# 12_Raspbbery_CM3.net
KiCad netlist of a schematic drawn in Altium Designer
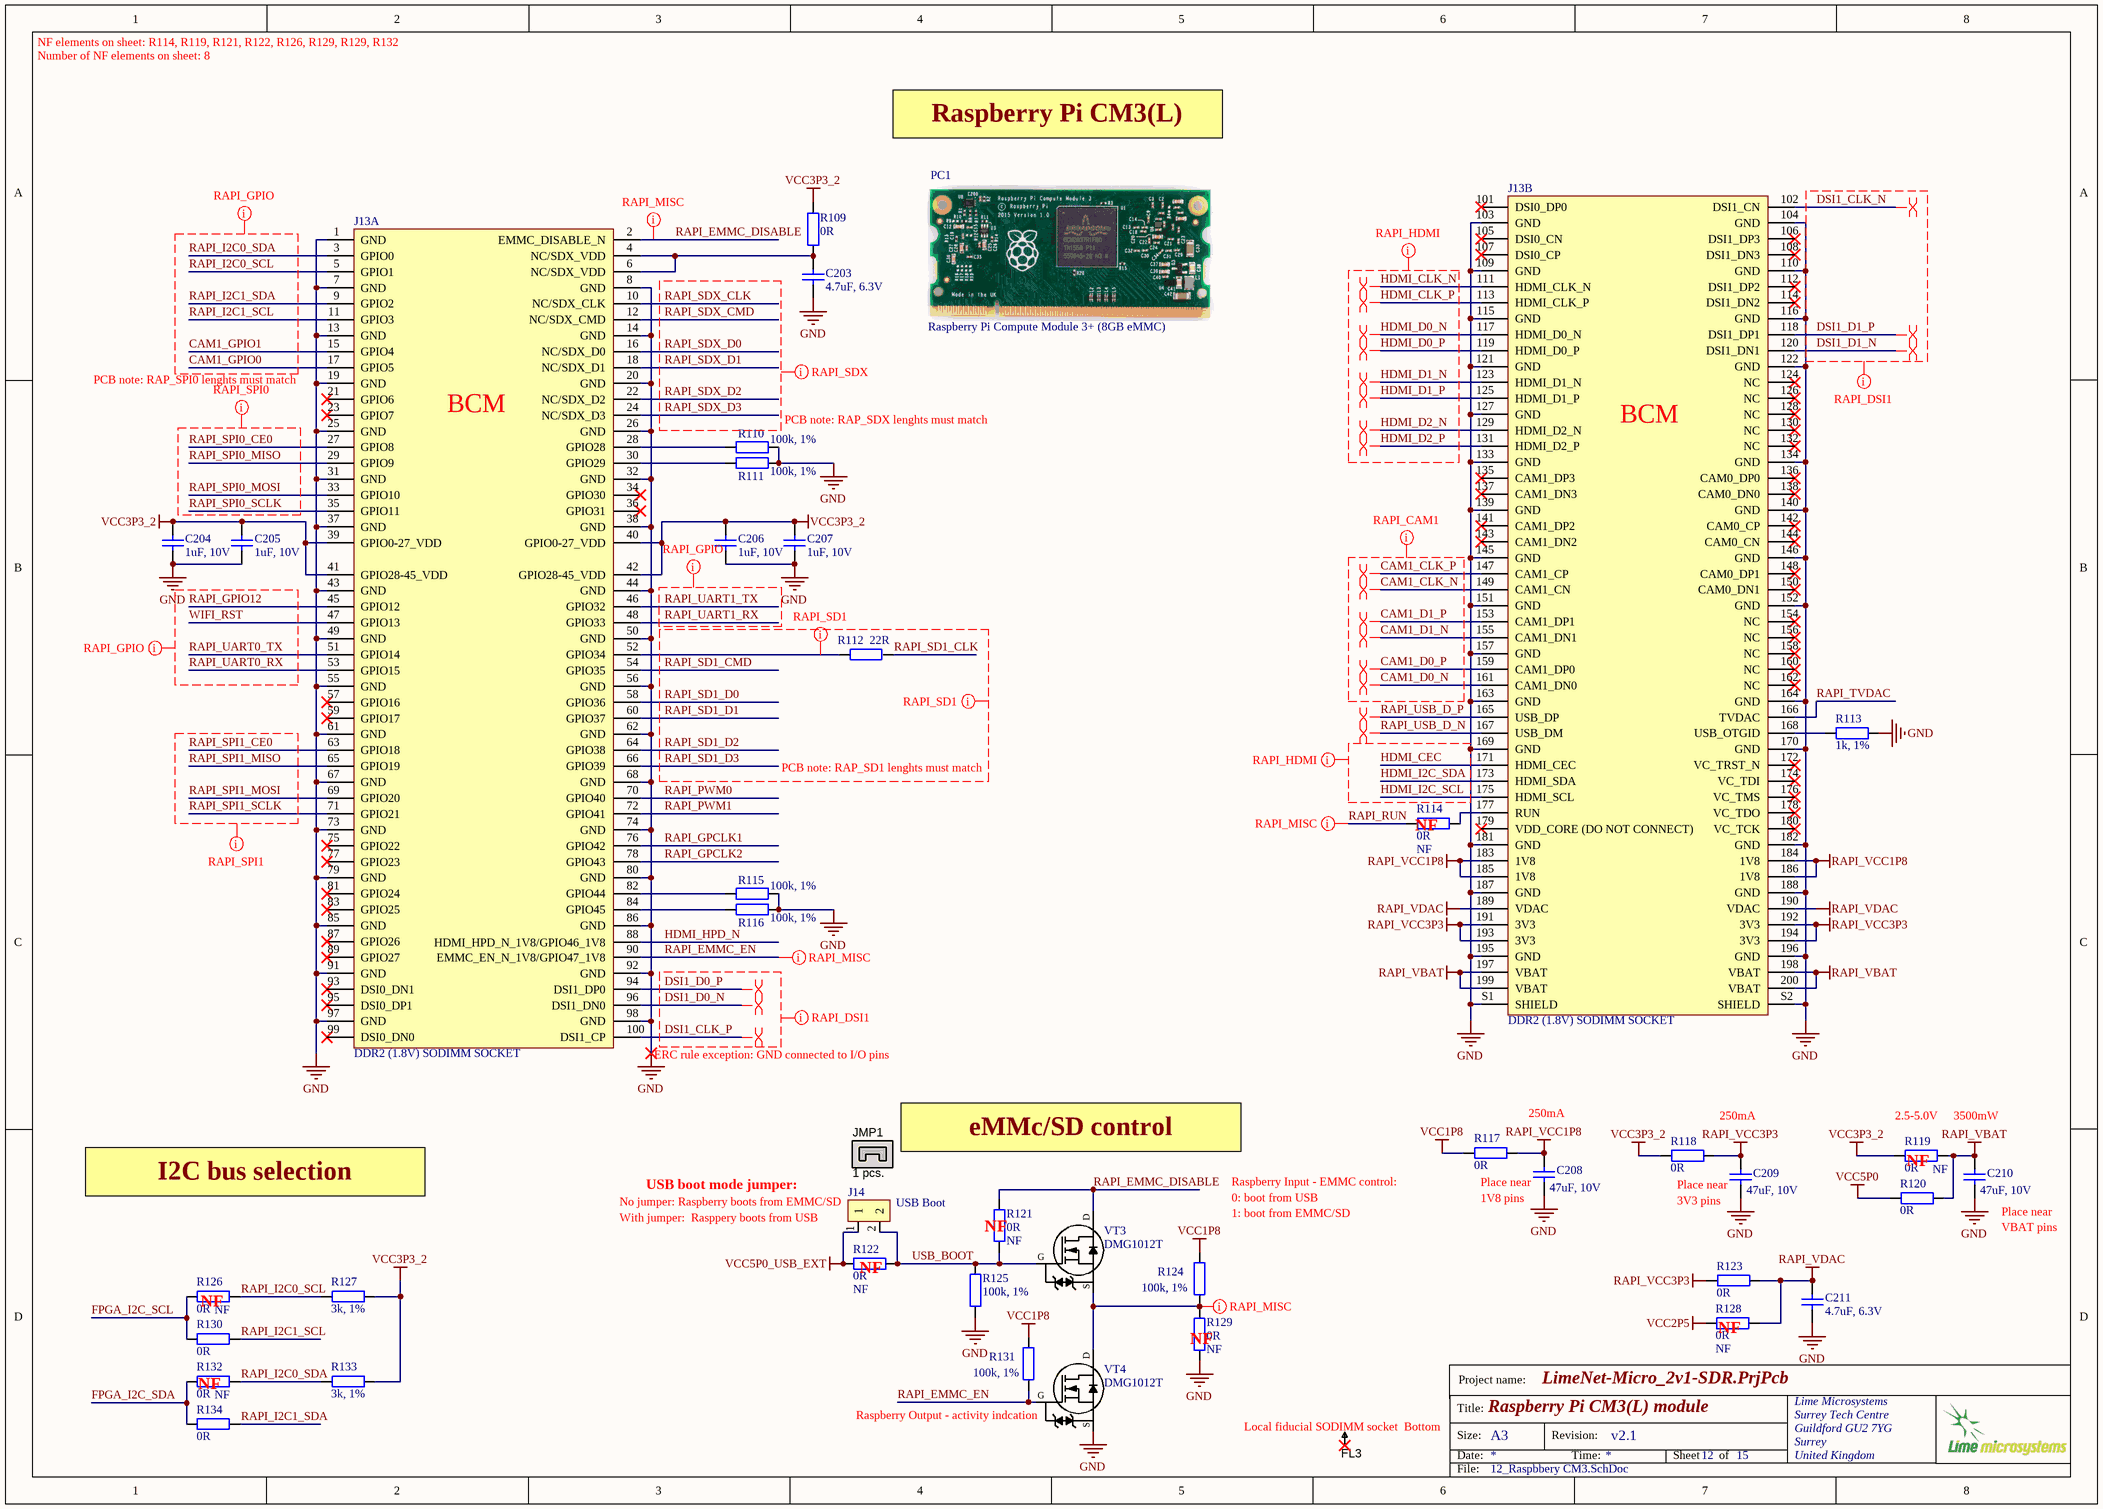
[diagram p0: 12_Raspbbery CM3.SchDoc]

(export (version "E")
  (design (tool "Eeschema 10.0.6"))
  (components
    (comp (ref "C203")
      (value "4.7uF, 6.3V")
      (footprint "CAP0402")
      (fields
        (field (name "MANUFACTURER") "Murata Electronics North America")
        (field (name "TOLERANCE") "±20%")
      )
      (libsource (lib "LimeMicroAltiumLib_schLib") (part "Cap_0402"))
    )
    (comp (ref "C204")
      (value "1uF, 10V")
      (footprint "CAP0402")
      (description "CAP CER 1UF 10V X5R 0402")
      (fields (field (name "MANUFACTURER") "Yageo") (field (name "TOLERANCE") "±20%"))
      (libsource (lib "LimeMicroAltiumLib_schLib") (part "Cap_0402"))
    )
    (comp (ref "C205")
      (value "1uF, 10V")
      (footprint "CAP0402")
      (description "CAP CER 1UF 10V X5R 0402")
      (fields (field (name "MANUFACTURER") "Yageo") (field (name "TOLERANCE") "±20%"))
      (libsource (lib "LimeMicroAltiumLib_schLib") (part "Cap_0402"))
    )
    (comp (ref "C206")
      (value "1uF, 10V")
      (footprint "CAP0402")
      (description "CAP CER 1UF 10V X5R 0402")
      (fields (field (name "MANUFACTURER") "Yageo") (field (name "TOLERANCE") "±20%"))
      (libsource (lib "LimeMicroAltiumLib_schLib") (part "Cap_0402"))
    )
    (comp (ref "C207")
      (value "1uF, 10V")
      (footprint "CAP0402")
      (description "CAP CER 1UF 10V X5R 0402")
      (fields (field (name "MANUFACTURER") "Yageo") (field (name "TOLERANCE") "±20%"))
      (libsource (lib "LimeMicroAltiumLib_schLib") (part "Cap_0402"))
    )
    (comp (ref "C208")
      (value "47uF, 10V")
      (footprint "CAP1206")
      (fields (field (name "TOLERANCE") "±20%") (field (name "MANUFACTURER") "TDK Corporation"))
      (libsource (lib "LimeFPGAboard_schLib") (part "Cap_1206"))
    )
    (comp (ref "C209")
      (value "47uF, 10V")
      (footprint "CAP1206")
      (fields (field (name "TOLERANCE") "±20%") (field (name "MANUFACTURER") "TDK Corporation"))
      (libsource (lib "LimeFPGAboard_schLib") (part "Cap_1206"))
    )
    (comp (ref "C210")
      (value "47uF, 10V")
      (footprint "CAP1206")
      (fields (field (name "TOLERANCE") "±20%") (field (name "MANUFACTURER") "TDK Corporation"))
      (libsource (lib "LimeFPGAboard_schLib") (part "Cap_1206"))
    )
    (comp (ref "C211")
      (value "4.7uF, 6.3V")
      (footprint "CAP0402")
      (fields
        (field (name "MANUFACTURER") "Murata Electronics North America")
        (field (name "TOLERANCE") "±20%")
      )
      (libsource (lib "LimeMicroAltiumLib_schLib") (part "Cap_0402"))
    )
    (comp (ref "FL3")
      (value "Fiducial")
      (footprint "Fiducial_local")
      (libsource (lib "VGTU_Altium_lib") (part "Fiducial"))
    )
    (comp (ref "J13")
      (value "DDR2 (1.8V) SODIMM SOCKET")
      (footprint "TE_1717254-1_DDR_SODIMM")
      (fields (field (name "MANUFACTURER") "TE Connectivity AMP Connectors"))
      (libsource (lib "LimeMicroAltiumLib_schLib_r01") (part "1717254-1"))
    )
    (comp (ref "J14")
      (value "USB Boot")
      (footprint "HDR_1x2")
      (fields (field (name "MANUFACTURER") "3M"))
      (libsource (lib "LimeFPGAboard_schLib") (part "Jumper"))
    )
    (comp (ref "JMP1")
      (value "1 pcs.")
      (description "Shorting Jumper, 2-position, 1.27mm pitch")
      (fields (field (name "MANUFACTURER") "Sullins"))
      (libsource (lib "LimeMicroAltiumLib_schLib") (part "JUMP_2P_CONN_HEADER"))
    )
    (comp (ref "PC1")
      (value "Raspberry Pi Compute Module 3+ (8GB eMMC)")
      (fields (field (name "MANUFACTURER") "RASPBERRY-PI"))
      (libsource (lib "LimeMicroAltiumLib_schLib_r01") (part "Raspberry_RPI-COMPUTE3"))
    )
    (comp (ref "R109")
      (value "0R")
      (footprint "RES0402")
      (fields (field (name "MANUFACTURER") "Yageo") (field (name "TOLERANCE") "Jumper"))
      (libsource (lib "LimeFPGAboard_schLib") (part "Res_0402"))
    )
    (comp (ref "R110")
      (value "100k, 1%")
      (footprint "RES0402")
      (fields
        (field (name "MANUFACTURER") "Vishay Dale")
        (field (name "TOLERANCE") "±1%")
        (field (name "MANUFACTURER PART NUMBER") "CRCW0402100KFKEDC")
      )
      (libsource (lib "LimeMicroAltiumLib_schLib") (part "Res_0402"))
    )
    (comp (ref "R111")
      (value "100k, 1%")
      (footprint "RES0402")
      (fields
        (field (name "MANUFACTURER") "Vishay Dale")
        (field (name "TOLERANCE") "±1%")
        (field (name "MANUFACTURER PART NUMBER") "CRCW0402100KFKEDC")
      )
      (libsource (lib "LimeMicroAltiumLib_schLib") (part "Res_0402"))
    )
    (comp (ref "R112")
      (value "22R")
      (footprint "RES0402")
      (fields (field (name "TOLERANCE") "±1%") (field (name "MANUFACTURER") "Yageo"))
      (libsource (lib "LimeFPGAboard_schLib") (part "Res_0402"))
    )
    (comp (ref "R113")
      (value "1k, 1%")
      (footprint "RES0402")
      (fields (field (name "MANUFACTURER") "Stackpole Electronics Inc") (field (name "TOLERANCE") "±1%"))
      (libsource (lib "LimeMicroAltiumLib_schLib") (part "Res_0402"))
    )
    (comp (ref "R114")
      (value "0R")
      (footprint "RES0402")
      (fields
        (field (name "MANUFACTURER") "Yageo")
        (field (name "ASSEMBLY INFO") "NF")
        (field (name "TOLERANCE") "Jumper")
      )
      (libsource (lib "LimeFPGAboard_schLib") (part "Res_0402"))
    )
    (comp (ref "R115")
      (value "100k, 1%")
      (footprint "RES0402")
      (fields
        (field (name "MANUFACTURER") "Vishay Dale")
        (field (name "TOLERANCE") "±1%")
        (field (name "MANUFACTURER PART NUMBER") "CRCW0402100KFKEDC")
      )
      (libsource (lib "LimeMicroAltiumLib_schLib") (part "Res_0402"))
    )
    (comp (ref "R116")
      (value "100k, 1%")
      (footprint "RES0402")
      (fields
        (field (name "MANUFACTURER") "Vishay Dale")
        (field (name "TOLERANCE") "±1%")
        (field (name "MANUFACTURER PART NUMBER") "CRCW0402100KFKEDC")
      )
      (libsource (lib "LimeMicroAltiumLib_schLib") (part "Res_0402"))
    )
    (comp (ref "R117")
      (value "0R")
      (footprint "RES0805")
      (fields (field (name "MANUFACTURER") "Vishay Dale") (field (name "TOLERANCE") "Jumper"))
      (libsource (lib "LimeMicroAltiumLib_schLib") (part "Res_0402"))
    )
    (comp (ref "R118")
      (value "0R")
      (footprint "RES0805")
      (fields (field (name "MANUFACTURER") "Vishay Dale") (field (name "TOLERANCE") "Jumper"))
      (libsource (lib "LimeMicroAltiumLib_schLib") (part "Res_0402"))
    )
    (comp (ref "R119")
      (value "0R")
      (footprint "RES0805")
      (fields
        (field (name "ASSEMBLY INFO") "NF")
        (field (name "MANUFACTURER") "Vishay Dale")
        (field (name "TOLERANCE") "Jumper")
      )
      (libsource (lib "LimeMicroAltiumLib_schLib") (part "Res_0402"))
    )
    (comp (ref "R120")
      (value "0R")
      (footprint "RES0805")
      (fields (field (name "MANUFACTURER") "Vishay Dale") (field (name "TOLERANCE") "Jumper"))
      (libsource (lib "LimeMicroAltiumLib_schLib") (part "Res_0402"))
    )
    (comp (ref "R121")
      (value "0R")
      (footprint "RES0402")
      (fields
        (field (name "MANUFACTURER") "Yageo")
        (field (name "ASSEMBLY INFO") "NF")
        (field (name "TOLERANCE") "Jumper")
      )
      (libsource (lib "LimeFPGAboard_schLib") (part "Res_0402"))
    )
    (comp (ref "R122")
      (value "0R")
      (footprint "RES0402")
      (fields
        (field (name "ASSEMBLY INFO") "NF")
        (field (name "MANUFACTURER") "Yageo")
        (field (name "TOLERANCE") "Jumper")
      )
      (libsource (lib "LimeMicroAltiumLib_schLib") (part "Res_0402"))
    )
    (comp (ref "R123")
      (value "0R")
      (footprint "RES0402")
      (fields (field (name "MANUFACTURER") "Yageo") (field (name "TOLERANCE") "Jumper"))
      (libsource (lib "LimeFPGAboard_schLib") (part "Res_0402"))
    )
    (comp (ref "R124")
      (value "100k, 1%")
      (footprint "RES0402")
      (fields
        (field (name "MANUFACTURER") "Vishay Dale")
        (field (name "TOLERANCE") "±1%")
        (field (name "MANUFACTURER PART NUMBER") "CRCW0402100KFKEDC")
      )
      (libsource (lib "LimeMicroAltiumLib_schLib") (part "Res_0402"))
    )
    (comp (ref "R125")
      (value "100k, 1%")
      (footprint "RES0402")
      (fields
        (field (name "MANUFACTURER") "Vishay Dale")
        (field (name "TOLERANCE") "±1%")
        (field (name "MANUFACTURER PART NUMBER") "CRCW0402100KFKEDC")
      )
      (libsource (lib "LimeMicroAltiumLib_schLib") (part "Res_0402"))
    )
    (comp (ref "R126")
      (value "0R")
      (footprint "RES0402")
      (fields
        (field (name "MANUFACTURER") "Yageo")
        (field (name "ASSEMBLY INFO") "NF")
        (field (name "TOLERANCE") "Jumper")
      )
      (libsource (lib "LimeFPGAboard_schLib") (part "Res_0402"))
    )
    (comp (ref "R127")
      (value "3k, 1%")
      (footprint "RES0402")
      (fields (field (name "TOLERANCE") "±1%") (field (name "MANUFACTURER") "Vishay Dale"))
      (libsource (lib "LimeMicroAltiumLib_schLib") (part "Res_0402"))
    )
    (comp (ref "R128")
      (value "0R")
      (footprint "RES0402")
      (fields
        (field (name "MANUFACTURER") "Yageo")
        (field (name "ASSEMBLY INFO") "NF")
        (field (name "TOLERANCE") "Jumper")
      )
      (libsource (lib "LimeFPGAboard_schLib") (part "Res_0402"))
    )
    (comp (ref "R129")
      (value "0R")
      (footprint "RES0402")
      (fields
        (field (name "MANUFACTURER") "Yageo")
        (field (name "ASSEMBLY INFO") "NF")
        (field (name "TOLERANCE") "Jumper")
      )
      (libsource (lib "LimeFPGAboard_schLib") (part "Res_0402"))
    )
    (comp (ref "R130")
      (value "0R")
      (footprint "RES0402")
      (fields (field (name "MANUFACTURER") "Yageo") (field (name "TOLERANCE") "Jumper"))
      (libsource (lib "LimeFPGAboard_schLib") (part "Res_0402"))
    )
    (comp (ref "R131")
      (value "100k, 1%")
      (footprint "RES0402")
      (fields
        (field (name "MANUFACTURER") "Vishay Dale")
        (field (name "TOLERANCE") "±1%")
        (field (name "MANUFACTURER PART NUMBER") "CRCW0402100KFKEDC")
      )
      (libsource (lib "LimeMicroAltiumLib_schLib") (part "Res_0402"))
    )
    (comp (ref "R132")
      (value "0R")
      (footprint "RES0402")
      (fields
        (field (name "MANUFACTURER") "Yageo")
        (field (name "ASSEMBLY INFO") "NF")
        (field (name "TOLERANCE") "Jumper")
      )
      (libsource (lib "LimeFPGAboard_schLib") (part "Res_0402"))
    )
    (comp (ref "R133")
      (value "3k, 1%")
      (footprint "RES0402")
      (fields (field (name "TOLERANCE") "±1%") (field (name "MANUFACTURER") "Vishay Dale"))
      (libsource (lib "LimeMicroAltiumLib_schLib") (part "Res_0402"))
    )
    (comp (ref "R134")
      (value "0R")
      (footprint "RES0402")
      (fields (field (name "MANUFACTURER") "Yageo") (field (name "TOLERANCE") "Jumper"))
      (libsource (lib "LimeFPGAboard_schLib") (part "Res_0402"))
    )
    (comp (ref "VT3")
      (value "DMG1012T")
      (footprint "SOT523")
      (fields (field (name "MANUFACTURER") "Diodes Incorporated"))
      (libsource (lib "LimeMicroAltiumLib_schLib_r01") (part "DMG1012T"))
    )
    (comp (ref "VT4")
      (value "DMG1012T")
      (footprint "SOT523")
      (fields (field (name "MANUFACTURER") "Diodes Incorporated"))
      (libsource (lib "LimeMicroAltiumLib_schLib_r01") (part "DMG1012T"))
    )
  )
  (nets
    (net (code "1") (name "/CAM1_CLK_N") (class "Default")
      (node (ref "J13") (pin "149") (pinfunction "CAM1_CN_149") (pintype "passive"))
    )
    (net (code "2") (name "/CAM1_CLK_P") (class "Default")
      (node (ref "J13") (pin "147") (pinfunction "CAM1_CP_147") (pintype "passive"))
    )
    (net (code "3") (name "/CAM1_D0_N") (class "Default")
      (node (ref "J13") (pin "161") (pinfunction "CAM1_DN0_161") (pintype "passive"))
    )
    (net (code "4") (name "/CAM1_D0_P") (class "Default")
      (node (ref "J13") (pin "159") (pinfunction "CAM1_DP0_159") (pintype "passive"))
    )
    (net (code "5") (name "/CAM1_D1_N") (class "Default")
      (node (ref "J13") (pin "155") (pinfunction "CAM1_DN1_155") (pintype "passive"))
    )
    (net (code "6") (name "/CAM1_D1_P") (class "Default")
      (node (ref "J13") (pin "153") (pinfunction "CAM1_DP1_153") (pintype "passive"))
    )
    (net (code "7") (name "/CAM1_GPIO0") (class "Default")
      (node (ref "J13") (pin "17") (pinfunction "GPIO5_17") (pintype "passive"))
    )
    (net (code "8") (name "/CAM1_GPIO1") (class "Default")
      (node (ref "J13") (pin "15") (pinfunction "GPIO4_15") (pintype "passive"))
    )
    (net (code "9") (name "/DSI1_CLK_N") (class "Default")
      (node (ref "J13") (pin "102") (pinfunction "DSI1_CN_102") (pintype "passive"))
    )
    (net (code "10") (name "/DSI1_CLK_P") (class "Default")
      (node (ref "J13") (pin "100") (pinfunction "DSI1_CP_100") (pintype "passive"))
    )
    (net (code "11") (name "/DSI1_D0_N") (class "Default")
      (node (ref "J13") (pin "96") (pinfunction "DSI1_DN0_96") (pintype "passive"))
    )
    (net (code "12") (name "/DSI1_D0_P") (class "Default")
      (node (ref "J13") (pin "94") (pinfunction "DSI1_DP0_94") (pintype "passive"))
    )
    (net (code "13") (name "/DSI1_D1_N") (class "Default")
      (node (ref "J13") (pin "120") (pinfunction "DSI1_DN1_120") (pintype "passive"))
    )
    (net (code "14") (name "/DSI1_D1_P") (class "Default")
      (node (ref "J13") (pin "118") (pinfunction "DSI1_DP1_118") (pintype "passive"))
    )
    (net (code "15") (name "/FPGA_I2C_SCL") (class "Default")
      (node (ref "R126") (pin "1") (pinfunction "1_1") (pintype "passive"))
      (node (ref "R130") (pin "1") (pinfunction "1_1") (pintype "passive"))
    )
    (net (code "16") (name "/FPGA_I2C_SDA") (class "Default")
      (node (ref "R132") (pin "1") (pinfunction "1_1") (pintype "passive"))
      (node (ref "R134") (pin "1") (pinfunction "1_1") (pintype "passive"))
    )
    (net (code "17") (name "/HDMI_CEC") (class "Default")
      (node (ref "J13") (pin "171") (pinfunction "HDMI_CEC_171") (pintype "passive"))
    )
    (net (code "18") (name "/HDMI_CLK_N") (class "Default")
      (node (ref "J13") (pin "111") (pinfunction "HDMI_CLK_N_111") (pintype "passive"))
    )
    (net (code "19") (name "/HDMI_CLK_P") (class "Default")
      (node (ref "J13") (pin "113") (pinfunction "HDMI_CLK_P_113") (pintype "passive"))
    )
    (net (code "20") (name "/HDMI_D0_N") (class "Default")
      (node (ref "J13") (pin "117") (pinfunction "HDMI_D0_N_117") (pintype "passive"))
    )
    (net (code "21") (name "/HDMI_D0_P") (class "Default")
      (node (ref "J13") (pin "119") (pinfunction "HDMI_D0_P_119") (pintype "passive"))
    )
    (net (code "22") (name "/HDMI_D1_N") (class "Default")
      (node (ref "J13") (pin "123") (pinfunction "HDMI_D1_N_123") (pintype "passive"))
    )
    (net (code "23") (name "/HDMI_D1_P") (class "Default")
      (node (ref "J13") (pin "125") (pinfunction "HDMI_D1_P_125") (pintype "passive"))
    )
    (net (code "24") (name "/HDMI_D2_N") (class "Default")
      (node (ref "J13") (pin "129") (pinfunction "HDMI_D2_N_129") (pintype "passive"))
    )
    (net (code "25") (name "/HDMI_D2_P") (class "Default")
      (node (ref "J13") (pin "131") (pinfunction "HDMI_D2_P_131") (pintype "passive"))
    )
    (net (code "26") (name "/HDMI_HPD_N") (class "Default")
      (node (ref "J13") (pin "88") (pinfunction "HDMI_HPD_N_1V8/GPIO46_1V8_88") (pintype "passive"))
    )
    (net (code "27") (name "/HDMI_I2C_SCL") (class "Default")
      (node (ref "J13") (pin "175") (pinfunction "HDMI_SCL_175") (pintype "passive"))
    )
    (net (code "28") (name "/HDMI_I2C_SDA") (class "Default")
      (node (ref "J13") (pin "173") (pinfunction "HDMI_SDA_173") (pintype "passive"))
    )
    (net (code "29") (name "/RAPI_EMMC_DISABLE") (class "Default")
      (node (ref "J13") (pin "2") (pinfunction "EMMC_DISABLE_N_2") (pintype "passive"))
      (node (ref "R121") (pin "1") (pinfunction "1_1") (pintype "passive"))
      (node (ref "VT3") (pin "D") (pinfunction "D_D") (pintype "passive"))
    )
    (net (code "30") (name "/RAPI_EMMC_EN") (class "Default")
      (node (ref "J13") (pin "90") (pinfunction "EMMC_EN_N_1V8/GPIO47_1V8_90") (pintype "passive"))
      (node (ref "R131") (pin "2") (pinfunction "2_2") (pintype "passive"))
      (node (ref "VT4") (pin "G") (pinfunction "G_G") (pintype "passive"))
    )
    (net (code "31") (name "/RAPI_GPCLK1") (class "Default")
      (node (ref "J13") (pin "76") (pinfunction "GPIO42_76") (pintype "passive"))
    )
    (net (code "32") (name "/RAPI_GPCLK2") (class "Default")
      (node (ref "J13") (pin "78") (pinfunction "GPIO43_78") (pintype "passive"))
    )
    (net (code "33") (name "/RAPI_GPIO12") (class "Default")
      (node (ref "J13") (pin "45") (pinfunction "GPIO12_45") (pintype "passive"))
    )
    (net (code "34") (name "/RAPI_I2C0_SCL") (class "Default")
      (node (ref "J13") (pin "5") (pinfunction "GPIO1_5") (pintype "passive"))
      (node (ref "R126") (pin "2") (pinfunction "2_2") (pintype "passive"))
      (node (ref "R127") (pin "2") (pinfunction "2_2") (pintype "passive"))
    )
    (net (code "35") (name "/RAPI_I2C0_SDA") (class "Default")
      (node (ref "J13") (pin "3") (pinfunction "GPIO0_3") (pintype "passive"))
      (node (ref "R132") (pin "2") (pinfunction "2_2") (pintype "passive"))
      (node (ref "R133") (pin "2") (pinfunction "2_2") (pintype "passive"))
    )
    (net (code "36") (name "/RAPI_I2C1_SCL") (class "Default")
      (node (ref "J13") (pin "11") (pinfunction "GPIO3_11") (pintype "passive"))
      (node (ref "R130") (pin "2") (pinfunction "2_2") (pintype "passive"))
    )
    (net (code "37") (name "/RAPI_I2C1_SDA") (class "Default")
      (node (ref "J13") (pin "9") (pinfunction "GPIO2_9") (pintype "passive"))
      (node (ref "R134") (pin "2") (pinfunction "2_2") (pintype "passive"))
    )
    (net (code "38") (name "/RAPI_PWM0") (class "Default")
      (node (ref "J13") (pin "70") (pinfunction "GPIO40_70") (pintype "passive"))
    )
    (net (code "39") (name "/RAPI_PWM1") (class "Default")
      (node (ref "J13") (pin "72") (pinfunction "GPIO41_72") (pintype "passive"))
    )
    (net (code "40") (name "/RAPI_RUN") (class "Default")
      (node (ref "R114") (pin "2") (pinfunction "2_2") (pintype "passive"))
    )
    (net (code "41") (name "/RAPI_SD1_CLK") (class "Default")
      (node (ref "R112") (pin "2") (pinfunction "2_2") (pintype "passive"))
    )
    (net (code "42") (name "/RAPI_SD1_CMD") (class "Default")
      (node (ref "J13") (pin "54") (pinfunction "GPIO35_54") (pintype "passive"))
    )
    (net (code "43") (name "/RAPI_SD1_D0") (class "Default")
      (node (ref "J13") (pin "58") (pinfunction "GPIO36_58") (pintype "passive"))
    )
    (net (code "44") (name "/RAPI_SD1_D1") (class "Default")
      (node (ref "J13") (pin "60") (pinfunction "GPIO37_60") (pintype "passive"))
    )
    (net (code "45") (name "/RAPI_SD1_D2") (class "Default")
      (node (ref "J13") (pin "64") (pinfunction "GPIO38_64") (pintype "passive"))
    )
    (net (code "46") (name "/RAPI_SD1_D3") (class "Default")
      (node (ref "J13") (pin "66") (pinfunction "GPIO39_66") (pintype "passive"))
    )
    (net (code "47") (name "/RAPI_SDX_CLK") (class "Default")
      (node (ref "J13") (pin "10") (pinfunction "NC/SDX_CLK_10") (pintype "passive"))
    )
    (net (code "48") (name "/RAPI_SDX_CMD") (class "Default")
      (node (ref "J13") (pin "12") (pinfunction "NC/SDX_CMD_12") (pintype "passive"))
    )
    (net (code "49") (name "/RAPI_SDX_D0") (class "Default")
      (node (ref "J13") (pin "16") (pinfunction "NC/SDX_D0_16") (pintype "passive"))
    )
    (net (code "50") (name "/RAPI_SDX_D1") (class "Default")
      (node (ref "J13") (pin "18") (pinfunction "NC/SDX_D1_18") (pintype "passive"))
    )
    (net (code "51") (name "/RAPI_SDX_D2") (class "Default")
      (node (ref "J13") (pin "22") (pinfunction "NC/SDX_D2_22") (pintype "passive"))
    )
    (net (code "52") (name "/RAPI_SDX_D3") (class "Default")
      (node (ref "J13") (pin "24") (pinfunction "NC/SDX_D3_24") (pintype "passive"))
    )
    (net (code "53") (name "/RAPI_SPI0_CE0") (class "Default")
      (node (ref "J13") (pin "27") (pinfunction "GPIO8_27") (pintype "passive"))
    )
    (net (code "54") (name "/RAPI_SPI0_MISO") (class "Default")
      (node (ref "J13") (pin "29") (pinfunction "GPIO9_29") (pintype "passive"))
    )
    (net (code "55") (name "/RAPI_SPI0_MOSI") (class "Default")
      (node (ref "J13") (pin "33") (pinfunction "GPIO10_33") (pintype "passive"))
    )
    (net (code "56") (name "/RAPI_SPI0_SCLK") (class "Default")
      (node (ref "J13") (pin "35") (pinfunction "GPIO11_35") (pintype "passive"))
    )
    (net (code "57") (name "/RAPI_SPI1_CE0") (class "Default")
      (node (ref "J13") (pin "63") (pinfunction "GPIO18_63") (pintype "passive"))
    )
    (net (code "58") (name "/RAPI_SPI1_MISO") (class "Default")
      (node (ref "J13") (pin "65") (pinfunction "GPIO19_65") (pintype "passive"))
    )
    (net (code "59") (name "/RAPI_SPI1_MOSI") (class "Default")
      (node (ref "J13") (pin "69") (pinfunction "GPIO20_69") (pintype "passive"))
    )
    (net (code "60") (name "/RAPI_SPI1_SCLK") (class "Default")
      (node (ref "J13") (pin "71") (pinfunction "GPIO21_71") (pintype "passive"))
    )
    (net (code "61") (name "/RAPI_TVDAC") (class "Default")
      (node (ref "J13") (pin "166") (pinfunction "TVDAC_166") (pintype "passive"))
    )
    (net (code "62") (name "/RAPI_UART0_RX") (class "Default")
      (node (ref "J13") (pin "53") (pinfunction "GPIO15_53") (pintype "passive"))
    )
    (net (code "63") (name "/RAPI_UART0_TX") (class "Default")
      (node (ref "J13") (pin "51") (pinfunction "GPIO14_51") (pintype "passive"))
    )
    (net (code "64") (name "/RAPI_UART1_RX") (class "Default")
      (node (ref "J13") (pin "48") (pinfunction "GPIO33_48") (pintype "passive"))
    )
    (net (code "65") (name "/RAPI_UART1_TX") (class "Default")
      (node (ref "J13") (pin "46") (pinfunction "GPIO32_46") (pintype "passive"))
    )
    (net (code "66") (name "/RAPI_USB_D_N") (class "Default")
      (node (ref "J13") (pin "167") (pinfunction "USB_DM_167") (pintype "passive"))
    )
    (net (code "67") (name "/RAPI_USB_D_P") (class "Default")
      (node (ref "J13") (pin "165") (pinfunction "USB_DP_165") (pintype "passive"))
    )
    (net (code "68") (name "/USB_BOOT") (class "Default")
      (node (ref "J14") (pin "2") (pinfunction "2_2") (pintype "passive"))
      (node (ref "R121") (pin "2") (pinfunction "2_2") (pintype "passive"))
      (node (ref "R122") (pin "2") (pinfunction "2_2") (pintype "passive"))
      (node (ref "R125") (pin "1") (pinfunction "1_1") (pintype "passive"))
      (node (ref "VT3") (pin "G") (pinfunction "G_G") (pintype "passive"))
    )
    (net (code "69") (name "/WIFI_RST") (class "Default")
      (node (ref "J13") (pin "47") (pinfunction "GPIO13_47") (pintype "passive"))
    )
    (net (code "70") (name "GND") (class "Default")
      (node (ref "C203") (pin "2") (pinfunction "2_2") (pintype "passive"))
      (node (ref "C204") (pin "1") (pinfunction "1_1") (pintype "passive"))
      (node (ref "C205") (pin "1") (pinfunction "1_1") (pintype "passive"))
      (node (ref "C206") (pin "1") (pinfunction "1_1") (pintype "passive"))
      (node (ref "C207") (pin "1") (pinfunction "1_1") (pintype "passive"))
      (node (ref "C208") (pin "1") (pinfunction "1_1") (pintype "passive"))
      (node (ref "C209") (pin "1") (pinfunction "1_1") (pintype "passive"))
      (node (ref "C210") (pin "1") (pinfunction "1_1") (pintype "passive"))
      (node (ref "C211") (pin "1") (pinfunction "1_1") (pintype "passive"))
      (node (ref "J13") (pin "1") (pinfunction "GND_1") (pintype "passive"))
      (node (ref "J13") (pin "103") (pinfunction "GND_103") (pintype "passive"))
      (node (ref "J13") (pin "104") (pinfunction "GND_104") (pintype "passive"))
      (node (ref "J13") (pin "109") (pinfunction "GND_109") (pintype "passive"))
      (node (ref "J13") (pin "110") (pinfunction "GND_110") (pintype "passive"))
      (node (ref "J13") (pin "115") (pinfunction "GND_115") (pintype "passive"))
      (node (ref "J13") (pin "116") (pinfunction "GND_116") (pintype "passive"))
      (node (ref "J13") (pin "121") (pinfunction "GND_121") (pintype "passive"))
      (node (ref "J13") (pin "122") (pinfunction "GND_122") (pintype "passive"))
      (node (ref "J13") (pin "127") (pinfunction "GND_127") (pintype "passive"))
      (node (ref "J13") (pin "13") (pinfunction "GND_13") (pintype "passive"))
      (node (ref "J13") (pin "133") (pinfunction "GND_133") (pintype "passive"))
      (node (ref "J13") (pin "134") (pinfunction "GND_134") (pintype "passive"))
      (node (ref "J13") (pin "139") (pinfunction "GND_139") (pintype "passive"))
      (node (ref "J13") (pin "14") (pinfunction "GND_14") (pintype "passive"))
      (node (ref "J13") (pin "140") (pinfunction "GND_140") (pintype "passive"))
      (node (ref "J13") (pin "145") (pinfunction "GND_145") (pintype "passive"))
      (node (ref "J13") (pin "146") (pinfunction "GND_146") (pintype "passive"))
      (node (ref "J13") (pin "151") (pinfunction "GND_151") (pintype "passive"))
      (node (ref "J13") (pin "152") (pinfunction "GND_152") (pintype "passive"))
      (node (ref "J13") (pin "157") (pinfunction "GND_157") (pintype "passive"))
      (node (ref "J13") (pin "163") (pinfunction "GND_163") (pintype "passive"))
      (node (ref "J13") (pin "164") (pinfunction "GND_164") (pintype "passive"))
      (node (ref "J13") (pin "169") (pinfunction "GND_169") (pintype "passive"))
      (node (ref "J13") (pin "170") (pinfunction "GND_170") (pintype "passive"))
      (node (ref "J13") (pin "181") (pinfunction "GND_181") (pintype "passive"))
      (node (ref "J13") (pin "182") (pinfunction "GND_182") (pintype "passive"))
      (node (ref "J13") (pin "187") (pinfunction "GND_187") (pintype "passive"))
      (node (ref "J13") (pin "188") (pinfunction "GND_188") (pintype "passive"))
      (node (ref "J13") (pin "19") (pinfunction "GND_19") (pintype "passive"))
      (node (ref "J13") (pin "195") (pinfunction "GND_195") (pintype "passive"))
      (node (ref "J13") (pin "196") (pinfunction "GND_196") (pintype "passive"))
      (node (ref "J13") (pin "20") (pinfunction "GND_20") (pintype "passive"))
      (node (ref "J13") (pin "25") (pinfunction "GND_25") (pintype "passive"))
      (node (ref "J13") (pin "26") (pinfunction "GND_26") (pintype "passive"))
      (node (ref "J13") (pin "31") (pinfunction "GND_31") (pintype "passive"))
      (node (ref "J13") (pin "32") (pinfunction "GND_32") (pintype "passive"))
      (node (ref "J13") (pin "37") (pinfunction "GND_37") (pintype "passive"))
      (node (ref "J13") (pin "38") (pinfunction "GND_38") (pintype "passive"))
      (node (ref "J13") (pin "43") (pinfunction "GND_43") (pintype "passive"))
      (node (ref "J13") (pin "44") (pinfunction "GND_44") (pintype "passive"))
      (node (ref "J13") (pin "49") (pinfunction "GND_49") (pintype "passive"))
      (node (ref "J13") (pin "50") (pinfunction "GND_50") (pintype "passive"))
      (node (ref "J13") (pin "55") (pinfunction "GND_55") (pintype "passive"))
      (node (ref "J13") (pin "56") (pinfunction "GND_56") (pintype "passive"))
      (node (ref "J13") (pin "61") (pinfunction "GND_61") (pintype "passive"))
      (node (ref "J13") (pin "62") (pinfunction "GND_62") (pintype "passive"))
      (node (ref "J13") (pin "67") (pinfunction "GND_67") (pintype "passive"))
      (node (ref "J13") (pin "68") (pinfunction "GND_68") (pintype "passive"))
      (node (ref "J13") (pin "7") (pinfunction "GND_7") (pintype "passive"))
      (node (ref "J13") (pin "73") (pinfunction "GND_73") (pintype "passive"))
      (node (ref "J13") (pin "74") (pinfunction "GND_74") (pintype "passive"))
      (node (ref "J13") (pin "79") (pinfunction "GND_79") (pintype "passive"))
      (node (ref "J13") (pin "8") (pinfunction "GND_8") (pintype "passive"))
      (node (ref "J13") (pin "80") (pinfunction "GND_80") (pintype "passive"))
      (node (ref "J13") (pin "85") (pinfunction "GND_85") (pintype "passive"))
      (node (ref "J13") (pin "86") (pinfunction "GND_86") (pintype "passive"))
      (node (ref "J13") (pin "91") (pinfunction "GND_91") (pintype "passive"))
      (node (ref "J13") (pin "92") (pinfunction "GND_92") (pintype "passive"))
      (node (ref "J13") (pin "97") (pinfunction "GND_97") (pintype "passive"))
      (node (ref "J13") (pin "98") (pinfunction "GND_98") (pintype "passive"))
      (node (ref "J13") (pin "S1") (pinfunction "SHIELD_S1") (pintype "passive"))
      (node (ref "J13") (pin "S2") (pinfunction "SHIELD_S2") (pintype "passive"))
      (node (ref "R110") (pin "1") (pinfunction "1_1") (pintype "passive"))
      (node (ref "R111") (pin "1") (pinfunction "1_1") (pintype "passive"))
      (node (ref "R113") (pin "1") (pinfunction "1_1") (pintype "passive"))
      (node (ref "R115") (pin "1") (pinfunction "1_1") (pintype "passive"))
      (node (ref "R116") (pin "1") (pinfunction "1_1") (pintype "passive"))
      (node (ref "R125") (pin "2") (pinfunction "2_2") (pintype "passive"))
      (node (ref "R129") (pin "1") (pinfunction "1_1") (pintype "passive"))
      (node (ref "VT4") (pin "S") (pinfunction "S_S") (pintype "passive"))
    )
    (net (code "71") (name "Net-(C203-Pad1)") (class "Default")
      (node (ref "C203") (pin "1") (pinfunction "1_1") (pintype "passive"))
      (node (ref "J13") (pin "4") (pinfunction "NC/SDX_VDD_4") (pintype "passive"))
      (node (ref "J13") (pin "6") (pinfunction "NC/SDX_VDD_6") (pintype "passive"))
      (node (ref "R109") (pin "1") (pinfunction "1_1") (pintype "passive"))
    )
    (net (code "72") (name "Net-(J13A-GPIO28)") (class "Default")
      (node (ref "J13") (pin "28") (pinfunction "GPIO28_28") (pintype "passive"))
      (node (ref "R110") (pin "2") (pinfunction "2_2") (pintype "passive"))
    )
    (net (code "73") (name "Net-(J13A-GPIO29)") (class "Default")
      (node (ref "J13") (pin "30") (pinfunction "GPIO29_30") (pintype "passive"))
      (node (ref "R111") (pin "2") (pinfunction "2_2") (pintype "passive"))
    )
    (net (code "74") (name "Net-(J13A-GPIO34)") (class "Default")
      (node (ref "J13") (pin "52") (pinfunction "GPIO34_52") (pintype "passive"))
      (node (ref "R112") (pin "1") (pinfunction "1_1") (pintype "passive"))
    )
    (net (code "75") (name "Net-(J13A-GPIO44)") (class "Default")
      (node (ref "J13") (pin "82") (pinfunction "GPIO44_82") (pintype "passive"))
      (node (ref "R115") (pin "2") (pinfunction "2_2") (pintype "passive"))
    )
    (net (code "76") (name "Net-(J13A-GPIO45)") (class "Default")
      (node (ref "J13") (pin "84") (pinfunction "GPIO45_84") (pintype "passive"))
      (node (ref "R116") (pin "2") (pinfunction "2_2") (pintype "passive"))
    )
    (net (code "77") (name "Net-(J13B-RUN)") (class "Default")
      (node (ref "J13") (pin "177") (pinfunction "RUN_177") (pintype "passive"))
      (node (ref "R114") (pin "1") (pinfunction "1_1") (pintype "passive"))
    )
    (net (code "78") (name "Net-(J13B-USB_OTGID)") (class "Default")
      (node (ref "J13") (pin "168") (pinfunction "USB_OTGID_168") (pintype "passive"))
      (node (ref "R113") (pin "2") (pinfunction "2_2") (pintype "passive"))
    )
    (net (code "79") (name "Net-(R124-Pad2)") (class "Default")
      (node (ref "R124") (pin "2") (pinfunction "2_2") (pintype "passive"))
      (node (ref "R129") (pin "2") (pinfunction "2_2") (pintype "passive"))
      (node (ref "VT3") (pin "S") (pinfunction "S_S") (pintype "passive"))
      (node (ref "VT4") (pin "D") (pinfunction "D_D") (pintype "passive"))
    )
    (net (code "80") (name "RAPI_VBAT") (class "Default")
      (node (ref "C210") (pin "2") (pinfunction "2_2") (pintype "passive"))
      (node (ref "J13") (pin "197") (pinfunction "VBAT_197") (pintype "passive"))
      (node (ref "J13") (pin "198") (pinfunction "VBAT_198") (pintype "passive"))
      (node (ref "J13") (pin "199") (pinfunction "VBAT_199") (pintype "passive"))
      (node (ref "J13") (pin "200") (pinfunction "VBAT_200") (pintype "passive"))
      (node (ref "R119") (pin "1") (pinfunction "1_1") (pintype "passive"))
      (node (ref "R120") (pin "1") (pinfunction "1_1") (pintype "passive"))
    )
    (net (code "81") (name "RAPI_VCC1P8") (class "Default")
      (node (ref "C208") (pin "2") (pinfunction "2_2") (pintype "passive"))
      (node (ref "J13") (pin "183") (pinfunction "1V8_183") (pintype "passive"))
      (node (ref "J13") (pin "184") (pinfunction "1V8_184") (pintype "passive"))
      (node (ref "J13") (pin "185") (pinfunction "1V8_185") (pintype "passive"))
      (node (ref "J13") (pin "186") (pinfunction "1V8_186") (pintype "passive"))
      (node (ref "R117") (pin "1") (pinfunction "1_1") (pintype "passive"))
    )
    (net (code "82") (name "RAPI_VCC3P3") (class "Default")
      (node (ref "C209") (pin "2") (pinfunction "2_2") (pintype "passive"))
      (node (ref "J13") (pin "191") (pinfunction "3V3_191") (pintype "passive"))
      (node (ref "J13") (pin "192") (pinfunction "3V3_192") (pintype "passive"))
      (node (ref "J13") (pin "193") (pinfunction "3V3_193") (pintype "passive"))
      (node (ref "J13") (pin "194") (pinfunction "3V3_194") (pintype "passive"))
      (node (ref "R118") (pin "1") (pinfunction "1_1") (pintype "passive"))
      (node (ref "R123") (pin "2") (pinfunction "2_2") (pintype "passive"))
    )
    (net (code "83") (name "RAPI_VDAC") (class "Default")
      (node (ref "C211") (pin "2") (pinfunction "2_2") (pintype "passive"))
      (node (ref "J13") (pin "189") (pinfunction "VDAC_189") (pintype "passive"))
      (node (ref "J13") (pin "190") (pinfunction "VDAC_190") (pintype "passive"))
      (node (ref "R123") (pin "1") (pinfunction "1_1") (pintype "passive"))
      (node (ref "R128") (pin "2") (pinfunction "2_2") (pintype "passive"))
    )
    (net (code "84") (name "VCC1P8") (class "Default")
      (node (ref "R117") (pin "2") (pinfunction "2_2") (pintype "passive"))
      (node (ref "R124") (pin "1") (pinfunction "1_1") (pintype "passive"))
      (node (ref "R131") (pin "1") (pinfunction "1_1") (pintype "passive"))
    )
    (net (code "85") (name "VCC2P5") (class "Default")
      (node (ref "R128") (pin "1") (pinfunction "1_1") (pintype "passive"))
    )
    (net (code "86") (name "VCC3P3_2") (class "Default")
      (node (ref "C204") (pin "2") (pinfunction "2_2") (pintype "passive"))
      (node (ref "C205") (pin "2") (pinfunction "2_2") (pintype "passive"))
      (node (ref "C206") (pin "2") (pinfunction "2_2") (pintype "passive"))
      (node (ref "C207") (pin "2") (pinfunction "2_2") (pintype "passive"))
      (node (ref "J13") (pin "39") (pinfunction "GPIO0-27_VDD_39") (pintype "passive"))
      (node (ref "J13") (pin "40") (pinfunction "GPIO0-27_VDD_40") (pintype "passive"))
      (node (ref "J13") (pin "41") (pinfunction "GPIO28-45_VDD_41") (pintype "passive"))
      (node (ref "J13") (pin "42") (pinfunction "GPIO28-45_VDD_42") (pintype "passive"))
      (node (ref "R109") (pin "2") (pinfunction "2_2") (pintype "passive"))
      (node (ref "R118") (pin "2") (pinfunction "2_2") (pintype "passive"))
      (node (ref "R119") (pin "2") (pinfunction "2_2") (pintype "passive"))
      (node (ref "R127") (pin "1") (pinfunction "1_1") (pintype "passive"))
      (node (ref "R133") (pin "1") (pinfunction "1_1") (pintype "passive"))
    )
    (net (code "87") (name "VCC5P0") (class "Default")
      (node (ref "R120") (pin "2") (pinfunction "2_2") (pintype "passive"))
    )
    (net (code "88") (name "VCC5P0_USB_EXT") (class "Default")
      (node (ref "J14") (pin "1") (pinfunction "1_1") (pintype "passive"))
      (node (ref "R122") (pin "1") (pinfunction "1_1") (pintype "passive"))
    )
    (net (code "89") (name "unconnected-(FL3-Pad1)") (class "Default")
      (node (ref "FL3") (pin "1") (pintype "passive+no_connect"))
    )
    (net (code "90") (name "unconnected-(J13A-DSI0_DN0-Pad99)") (class "Default")
      (node (ref "J13") (pin "99") (pinfunction "DSI0_DN0_99") (pintype "passive+no_connect"))
    )
    (net (code "91") (name "unconnected-(J13A-DSI0_DN1-Pad93)") (class "Default")
      (node (ref "J13") (pin "93") (pinfunction "DSI0_DN1_93") (pintype "passive+no_connect"))
    )
    (net (code "92") (name "unconnected-(J13A-DSI0_DP1-Pad95)") (class "Default")
      (node (ref "J13") (pin "95") (pinfunction "DSI0_DP1_95") (pintype "passive+no_connect"))
    )
    (net (code "93") (name "unconnected-(J13A-GPIO6-Pad21)") (class "Default")
      (node (ref "J13") (pin "21") (pinfunction "GPIO6_21") (pintype "passive+no_connect"))
    )
    (net (code "94") (name "unconnected-(J13A-GPIO7-Pad23)") (class "Default")
      (node (ref "J13") (pin "23") (pinfunction "GPIO7_23") (pintype "passive+no_connect"))
    )
    (net (code "95") (name "unconnected-(J13A-GPIO16-Pad57)") (class "Default")
      (node (ref "J13") (pin "57") (pinfunction "GPIO16_57") (pintype "passive+no_connect"))
    )
    (net (code "96") (name "unconnected-(J13A-GPIO17-Pad59)") (class "Default")
      (node (ref "J13") (pin "59") (pinfunction "GPIO17_59") (pintype "passive+no_connect"))
    )
    (net (code "97") (name "unconnected-(J13A-GPIO22-Pad75)") (class "Default")
      (node (ref "J13") (pin "75") (pinfunction "GPIO22_75") (pintype "passive+no_connect"))
    )
    (net (code "98") (name "unconnected-(J13A-GPIO23-Pad77)") (class "Default")
      (node (ref "J13") (pin "77") (pinfunction "GPIO23_77") (pintype "passive+no_connect"))
    )
    (net (code "99") (name "unconnected-(J13A-GPIO24-Pad81)") (class "Default")
      (node (ref "J13") (pin "81") (pinfunction "GPIO24_81") (pintype "passive+no_connect"))
    )
    (net (code "100") (name "unconnected-(J13A-GPIO25-Pad83)") (class "Default")
      (node (ref "J13") (pin "83") (pinfunction "GPIO25_83") (pintype "passive+no_connect"))
    )
    (net (code "101") (name "unconnected-(J13A-GPIO26-Pad87)") (class "Default")
      (node (ref "J13") (pin "87") (pinfunction "GPIO26_87") (pintype "passive+no_connect"))
    )
    (net (code "102") (name "unconnected-(J13A-GPIO27-Pad89)") (class "Default")
      (node (ref "J13") (pin "89") (pinfunction "GPIO27_89") (pintype "passive+no_connect"))
    )
    (net (code "103") (name "unconnected-(J13A-GPIO30-Pad34)") (class "Default")
      (node (ref "J13") (pin "34") (pinfunction "GPIO30_34") (pintype "passive+no_connect"))
    )
    (net (code "104") (name "unconnected-(J13A-GPIO31-Pad36)") (class "Default")
      (node (ref "J13") (pin "36") (pinfunction "GPIO31_36") (pintype "passive+no_connect"))
    )
    (net (code "105") (name "unconnected-(J13B-CAM0_CN-Pad144)") (class "Default")
      (node (ref "J13") (pin "144") (pinfunction "CAM0_CN_144") (pintype "passive+no_connect"))
    )
    (net (code "106") (name "unconnected-(J13B-CAM0_CP-Pad142)") (class "Default")
      (node (ref "J13") (pin "142") (pinfunction "CAM0_CP_142") (pintype "passive+no_connect"))
    )
    (net (code "107") (name "unconnected-(J13B-CAM0_DN0-Pad138)") (class "Default")
      (node (ref "J13") (pin "138") (pinfunction "CAM0_DN0_138") (pintype "passive+no_connect"))
    )
    (net (code "108") (name "unconnected-(J13B-CAM0_DN1-Pad150)") (class "Default")
      (node (ref "J13") (pin "150") (pinfunction "CAM0_DN1_150") (pintype "passive+no_connect"))
    )
    (net (code "109") (name "unconnected-(J13B-CAM0_DP0-Pad136)") (class "Default")
      (node (ref "J13") (pin "136") (pinfunction "CAM0_DP0_136") (pintype "passive+no_connect"))
    )
    (net (code "110") (name "unconnected-(J13B-CAM0_DP1-Pad148)") (class "Default")
      (node (ref "J13") (pin "148") (pinfunction "CAM0_DP1_148") (pintype "passive+no_connect"))
    )
    (net (code "111") (name "unconnected-(J13B-CAM1_DN2-Pad143)") (class "Default")
      (node (ref "J13") (pin "143") (pinfunction "CAM1_DN2_143") (pintype "passive+no_connect"))
    )
    (net (code "112") (name "unconnected-(J13B-CAM1_DN3-Pad137)") (class "Default")
      (node (ref "J13") (pin "137") (pinfunction "CAM1_DN3_137") (pintype "passive+no_connect"))
    )
    (net (code "113") (name "unconnected-(J13B-CAM1_DP2-Pad141)") (class "Default")
      (node (ref "J13") (pin "141") (pinfunction "CAM1_DP2_141") (pintype "passive+no_connect"))
    )
    (net (code "114") (name "unconnected-(J13B-CAM1_DP3-Pad135)") (class "Default")
      (node (ref "J13") (pin "135") (pinfunction "CAM1_DP3_135") (pintype "passive+no_connect"))
    )
    (net (code "115") (name "unconnected-(J13B-DSI0_CN-Pad105)") (class "Default")
      (node (ref "J13") (pin "105") (pinfunction "DSI0_CN_105") (pintype "passive+no_connect"))
    )
    (net (code "116") (name "unconnected-(J13B-DSI0_CP-Pad107)") (class "Default")
      (node (ref "J13") (pin "107") (pinfunction "DSI0_CP_107") (pintype "passive+no_connect"))
    )
    (net (code "117") (name "unconnected-(J13B-DSI0_DP0-Pad101)") (class "Default")
      (node (ref "J13") (pin "101") (pinfunction "DSI0_DP0_101") (pintype "passive+no_connect"))
    )
    (net (code "118") (name "unconnected-(J13B-DSI1_DN2-Pad114)") (class "Default")
      (node (ref "J13") (pin "114") (pinfunction "DSI1_DN2_114") (pintype "passive+no_connect"))
    )
    (net (code "119") (name "unconnected-(J13B-DSI1_DN3-Pad108)") (class "Default")
      (node (ref "J13") (pin "108") (pinfunction "DSI1_DN3_108") (pintype "passive+no_connect"))
    )
    (net (code "120") (name "unconnected-(J13B-DSI1_DP2-Pad112)") (class "Default")
      (node (ref "J13") (pin "112") (pinfunction "DSI1_DP2_112") (pintype "passive+no_connect"))
    )
    (net (code "121") (name "unconnected-(J13B-DSI1_DP3-Pad106)") (class "Default")
      (node (ref "J13") (pin "106") (pinfunction "DSI1_DP3_106") (pintype "passive+no_connect"))
    )
    (net (code "122") (name "unconnected-(J13B-NC-Pad124)") (class "Default")
      (node (ref "J13") (pin "124") (pinfunction "NC_124") (pintype "passive+no_connect"))
    )
    (net (code "123") (name "unconnected-(J13B-NC-Pad126)") (class "Default")
      (node (ref "J13") (pin "126") (pinfunction "NC_126") (pintype "passive+no_connect"))
    )
    (net (code "124") (name "unconnected-(J13B-NC-Pad128)") (class "Default")
      (node (ref "J13") (pin "128") (pinfunction "NC_128") (pintype "passive+no_connect"))
    )
    (net (code "125") (name "unconnected-(J13B-NC-Pad130)") (class "Default")
      (node (ref "J13") (pin "130") (pinfunction "NC_130") (pintype "passive+no_connect"))
    )
    (net (code "126") (name "unconnected-(J13B-NC-Pad132)") (class "Default")
      (node (ref "J13") (pin "132") (pinfunction "NC_132") (pintype "passive+no_connect"))
    )
    (net (code "127") (name "unconnected-(J13B-NC-Pad154)") (class "Default")
      (node (ref "J13") (pin "154") (pinfunction "NC_154") (pintype "passive+no_connect"))
    )
    (net (code "128") (name "unconnected-(J13B-NC-Pad156)") (class "Default")
      (node (ref "J13") (pin "156") (pinfunction "NC_156") (pintype "passive+no_connect"))
    )
    (net (code "129") (name "unconnected-(J13B-NC-Pad158)") (class "Default")
      (node (ref "J13") (pin "158") (pinfunction "NC_158") (pintype "passive+no_connect"))
    )
    (net (code "130") (name "unconnected-(J13B-NC-Pad160)") (class "Default")
      (node (ref "J13") (pin "160") (pinfunction "NC_160") (pintype "passive+no_connect"))
    )
    (net (code "131") (name "unconnected-(J13B-NC-Pad162)") (class "Default")
      (node (ref "J13") (pin "162") (pinfunction "NC_162") (pintype "passive+no_connect"))
    )
    (net (code "132") (name "unconnected-(J13B-VC_TCK-Pad180)") (class "Default")
      (node (ref "J13") (pin "180") (pinfunction "VC_TCK_180") (pintype "passive+no_connect"))
    )
    (net (code "133") (name "unconnected-(J13B-VC_TDI-Pad174)") (class "Default")
      (node (ref "J13") (pin "174") (pinfunction "VC_TDI_174") (pintype "passive+no_connect"))
    )
    (net (code "134") (name "unconnected-(J13B-VC_TDO-Pad178)") (class "Default")
      (node (ref "J13") (pin "178") (pinfunction "VC_TDO_178") (pintype "passive+no_connect"))
    )
    (net (code "135") (name "unconnected-(J13B-VC_TMS-Pad176)") (class "Default")
      (node (ref "J13") (pin "176") (pinfunction "VC_TMS_176") (pintype "passive+no_connect"))
    )
    (net (code "136") (name "unconnected-(J13B-VC_TRST_N-Pad172)") (class "Default")
      (node (ref "J13") (pin "172") (pinfunction "VC_TRST_N_172") (pintype "passive+no_connect"))
    )
    (net (code "137") (name "unconnected-(J13B-VDD_CORE_(DO_NOT_CONNECT)-Pad179)") (class "Default")
      (node (ref "J13") (pin "179") (pinfunction "VDD_CORE_(DO_NOT_CONNECT)_179") (pintype "passive+no_connect"))
    )
    (net (code "138") (name "unconnected-(JMP1-Pad1)") (class "Default")
      (node (ref "JMP1") (pin "1") (pinfunction "1_1") (pintype "passive"))
    )
    (net (code "139") (name "unconnected-(JMP1-Pad2)") (class "Default")
      (node (ref "JMP1") (pin "2") (pinfunction "2_2") (pintype "passive"))
    )
  )
)
